# aq_mx_v1-3-0c.net
KiCad netlist of a schematic drawn in EAGLE
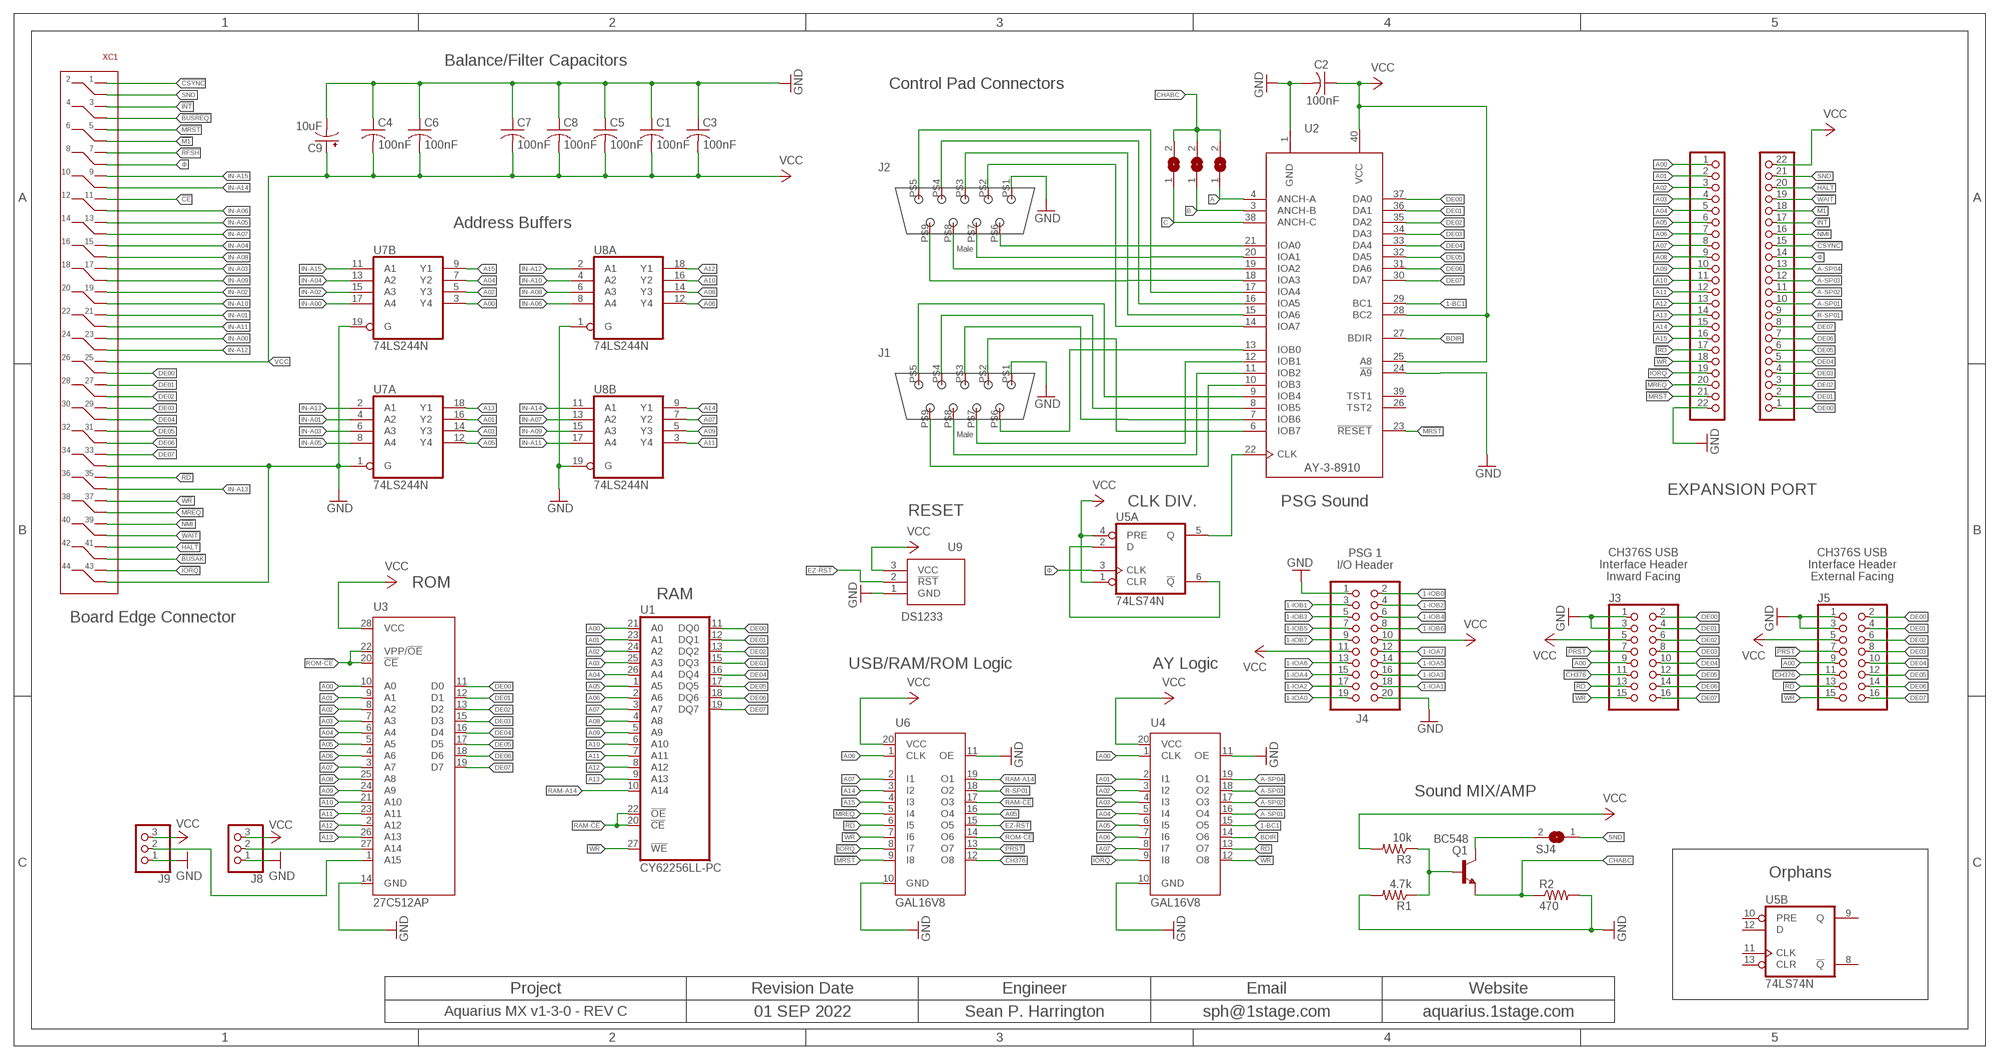
[diagram p0: schematic, sheet 1]

(export (version "E")
  (design (tool "Eeschema 10.0.6"))
  (components
    (comp (ref "C1")
      (value "100nF")
      (footprint "eagle-import:C050-025X075")
      (libsource (lib "eagle-import") (part "C-US050-025X075"))
    )
    (comp (ref "C2")
      (value "100nF")
      (footprint "eagle-import:C050-025X075")
      (libsource (lib "eagle-import") (part "C-US050-025X075"))
    )
    (comp (ref "C3")
      (value "100nF")
      (footprint "eagle-import:C050-025X075")
      (libsource (lib "eagle-import") (part "C-US050-025X075"))
    )
    (comp (ref "C4")
      (value "100nF")
      (footprint "eagle-import:C050-025X075")
      (libsource (lib "eagle-import") (part "C-US050-025X075"))
    )
    (comp (ref "C5")
      (value "100nF")
      (footprint "eagle-import:C050-025X075")
      (libsource (lib "eagle-import") (part "C-US050-025X075"))
    )
    (comp (ref "C6")
      (value "100nF")
      (footprint "eagle-import:C050-025X075")
      (libsource (lib "eagle-import") (part "C-US050-025X075"))
    )
    (comp (ref "C7")
      (value "100nF")
      (footprint "eagle-import:C050-025X075")
      (libsource (lib "eagle-import") (part "C-US050-025X075"))
    )
    (comp (ref "C8")
      (value "100nF")
      (footprint "eagle-import:C050-025X075")
      (libsource (lib "eagle-import") (part "C-US050-025X075"))
    )
    (comp (ref "C9")
      (value "10uF")
      (footprint "eagle-import:E22-6")
      (libsource (lib "eagle-import") (part "CPOL-USE22-6AXIAL"))
    )
    (comp (ref "J1")
      (value "DB9-MALE-RA")
      (footprint "eagle-import:DB9-MALE-RA")
      (libsource (lib "eagle-import") (part "DB9-MALE-RA"))
    )
    (comp (ref "J2")
      (value "DB9-MALE-RA")
      (footprint "eagle-import:DB9-MALE-RA")
      (libsource (lib "eagle-import") (part "DB9-MALE-RA"))
    )
    (comp (ref "J3")
      (value "PINHD-2X8")
      (footprint "eagle-import:2X08")
      (libsource (lib "eagle-import") (part "PINHD-2X8"))
    )
    (comp (ref "J4")
      (value "PINHD-2X10")
      (footprint "eagle-import:2X10")
      (libsource (lib "eagle-import") (part "PINHD-2X10"))
    )
    (comp (ref "J5")
      (value "PINHD-2X8")
      (footprint "eagle-import:2X08")
      (libsource (lib "eagle-import") (part "PINHD-2X8"))
    )
    (comp (ref "J6")
      (value "PINHD-1X22")
      (footprint "eagle-import:1X22")
      (libsource (lib "eagle-import") (part "PINHD-1X22"))
    )
    (comp (ref "J7")
      (value "PINHD-1X22")
      (footprint "eagle-import:1X22")
      (libsource (lib "eagle-import") (part "PINHD-1X22"))
    )
    (comp (ref "J8")
      (value "PINHD-1X3")
      (footprint "eagle-import:1X03")
      (libsource (lib "eagle-import") (part "PINHD-1X3"))
    )
    (comp (ref "J9")
      (value "PINHD-1X3")
      (footprint "eagle-import:1X03")
      (libsource (lib "eagle-import") (part "PINHD-1X3"))
    )
    (comp (ref "Q1")
      (value "BC548")
      (footprint "eagle-import:TO92-CBE")
      (libsource (lib "eagle-import") (part "-NPN-TO92-CBEBC548"))
    )
    (comp (ref "R1")
      (value "4.7k")
      (footprint "eagle-import:0204_7")
      (libsource (lib "eagle-import") (part "R-US_0204/7"))
    )
    (comp (ref "R2")
      (value "470")
      (footprint "eagle-import:0204_7")
      (libsource (lib "eagle-import") (part "R-US_0204/7"))
    )
    (comp (ref "R3")
      (value "10k")
      (footprint "eagle-import:0204_7")
      (libsource (lib "eagle-import") (part "R-US_0204/7"))
    )
    (comp (ref "SJ1") (value "SJ") (footprint "eagle-import:SJ") (libsource (lib "eagle-import") (part "SJ")))
    (comp (ref "SJ2") (value "SJ") (footprint "eagle-import:SJ") (libsource (lib "eagle-import") (part "SJ")))
    (comp (ref "SJ3") (value "SJ") (footprint "eagle-import:SJ") (libsource (lib "eagle-import") (part "SJ")))
    (comp (ref "SJ4") (value "SJ") (footprint "eagle-import:SJ") (libsource (lib "eagle-import") (part "SJ")))
    (comp (ref "U1")
      (value "CY62256LL-PC")
      (footprint "eagle-import:DIL28-6")
      (libsource (lib "eagle-import") (part "CY62256LL-?PC"))
    )
    (comp (ref "U2")
      (value "AY-3-8910")
      (footprint "eagle-import:RAD38910-DIL40-6")
      (libsource (lib "eagle-import") (part "RAD38910DIL40-6"))
    )
    (comp (ref "U3")
      (value "27C512AP")
      (footprint "eagle-import:DIL28-6")
      (fields (field (name "MPN") "M27C512-90B6"))
      (libsource (lib "eagle-import") (part "27512APC"))
    )
    (comp (ref "U4")
      (value "GAL16V8")
      (footprint "eagle-import:DIL20")
      (fields (field (name "MPN") "ATF16V8CZ-15PU"))
      (libsource (lib "eagle-import") (part "ATF16V8BP3"))
    )
    (comp (ref "U5")
      (value "74LS74N")
      (footprint "eagle-import:DIL14")
      (libsource (lib "eagle-import") (part "7474NLS"))
    )
    (comp (ref "U6")
      (value "GAL16V8")
      (footprint "eagle-import:DIL20")
      (fields (field (name "MPN") "ATF16V8CZ-15PU"))
      (libsource (lib "eagle-import") (part "ATF16V8BP3"))
    )
    (comp (ref "U7")
      (value "74LS244N")
      (footprint "eagle-import:DIL20")
      (libsource (lib "eagle-import") (part "74244NLS"))
    )
    (comp (ref "U8")
      (value "74LS244N")
      (footprint "eagle-import:DIL20")
      (libsource (lib "eagle-import") (part "74244NLS"))
    )
    (comp (ref "U9")
      (value "DS1233")
      (footprint "eagle-import:TO-92")
      (fields
        (field (name "ARROW_PART_NUMBER") "DS1233-10+")
        (field (name "MOUSER_PART_NUMBER") "700-DS1233-10")
      )
      (libsource (lib "eagle-import") (part "DS1233-10+"))
    )
    (comp (ref "XC1")
      (value "AQ-CART-EDGE")
      (footprint "eagle-import:AQ-CART-EDGE")
      (libsource (lib "eagle-import") (part "AQ-CART-EDGE"))
    )
  )
  (nets
    (net (code "1") (name "/EZ-~{RST}") (class "Default")
      (node (ref "U6") (pin "15") (pinfunction "O5_15") (pintype "output"))
      (node (ref "U9") (pin "2") (pinfunction "~{RST}_2") (pintype "input"))
    )
    (net (code "2") (name "/RAM-~{CE}") (class "Default")
      (node (ref "U1") (pin "20") (pinfunction "~{CE}_20") (pintype "input"))
      (node (ref "U1") (pin "22") (pinfunction "~{OE}_22") (pintype "input"))
      (node (ref "U6") (pin "17") (pinfunction "O3_17") (pintype "output"))
    )
    (net (code "3") (name "/ROM-~{CE}") (class "Default")
      (node (ref "U3") (pin "20") (pinfunction "~{CE}_20") (pintype "input"))
      (node (ref "U3") (pin "22") (pinfunction "VPP/~{OE}_22") (pintype "input"))
      (node (ref "U6") (pin "14") (pinfunction "O6_14") (pintype "output"))
    )
    (net (code "4") (name "/~{BUSAK}") (class "Default")
      (node (ref "XC1") (pin "P$42") (pinfunction "X42_P$42") (pintype "bidirectional"))
    )
    (net (code "5") (name "/~{BUSREQ}") (class "Default")
      (node (ref "XC1") (pin "P$4") (pinfunction "X4_P$4") (pintype "bidirectional"))
    )
    (net (code "6") (name "/~{CE}") (class "Default")
      (node (ref "XC1") (pin "P$11") (pinfunction "X11_P$11") (pintype "bidirectional"))
    )
    (net (code "7") (name "/~{CH376}") (class "Default")
      (node (ref "J3") (pin "11") (pinfunction "11_11") (pintype "passive"))
      (node (ref "J5") (pin "11") (pinfunction "11_11") (pintype "passive"))
      (node (ref "U6") (pin "12") (pinfunction "O8_12") (pintype "output"))
    )
    (net (code "8") (name "/~{CSYNC}") (class "Default")
      (node (ref "J6") (pin "15") (pinfunction "15_15") (pintype "passive"))
      (node (ref "XC1") (pin "P$1") (pinfunction "X1_P$1") (pintype "bidirectional"))
    )
    (net (code "9") (name "/~{HALT}") (class "Default")
      (node (ref "J6") (pin "20") (pinfunction "20_20") (pintype "passive"))
      (node (ref "XC1") (pin "P$41") (pinfunction "X41_P$41") (pintype "bidirectional"))
    )
    (net (code "10") (name "/~{INT}") (class "Default")
      (node (ref "J6") (pin "17") (pinfunction "17_17") (pintype "passive"))
      (node (ref "XC1") (pin "P$3") (pinfunction "X3_P$3") (pintype "bidirectional"))
    )
    (net (code "11") (name "/~{IORQ}") (class "Default")
      (node (ref "J7") (pin "19") (pinfunction "19_19") (pintype "passive"))
      (node (ref "U4") (pin "9") (pinfunction "I8_9") (pintype "input"))
      (node (ref "U6") (pin "8") (pinfunction "I7_8") (pintype "input"))
      (node (ref "XC1") (pin "P$43") (pinfunction "X43_P$43") (pintype "bidirectional"))
    )
    (net (code "12") (name "/~{M1}") (class "Default")
      (node (ref "J6") (pin "18") (pinfunction "18_18") (pintype "passive"))
      (node (ref "XC1") (pin "P$6") (pinfunction "X6_P$6") (pintype "bidirectional"))
    )
    (net (code "13") (name "/~{MREQ}") (class "Default")
      (node (ref "J7") (pin "20") (pinfunction "20_20") (pintype "passive"))
      (node (ref "U6") (pin "5") (pinfunction "I4_5") (pintype "input"))
      (node (ref "XC1") (pin "P$38") (pinfunction "X38_P$38") (pintype "bidirectional"))
    )
    (net (code "14") (name "/~{MRST}") (class "Default")
      (node (ref "J7") (pin "21") (pinfunction "21_21") (pintype "passive"))
      (node (ref "U2") (pin "23") (pinfunction "~{RESET}_23") (pintype "bidirectional"))
      (node (ref "U6") (pin "9") (pinfunction "I8_9") (pintype "input"))
      (node (ref "XC1") (pin "P$5") (pinfunction "X5_P$5") (pintype "bidirectional"))
    )
    (net (code "15") (name "/~{NMI}") (class "Default")
      (node (ref "J6") (pin "16") (pinfunction "16_16") (pintype "passive"))
      (node (ref "XC1") (pin "P$39") (pinfunction "X39_P$39") (pintype "bidirectional"))
    )
    (net (code "16") (name "/~{PRST}") (class "Default")
      (node (ref "J3") (pin "7") (pinfunction "7_7") (pintype "passive"))
      (node (ref "J5") (pin "7") (pinfunction "7_7") (pintype "passive"))
      (node (ref "U6") (pin "13") (pinfunction "O7_13") (pintype "output"))
    )
    (net (code "17") (name "/~{RD}") (class "Default")
      (node (ref "J3") (pin "13") (pinfunction "13_13") (pintype "passive"))
      (node (ref "J5") (pin "13") (pinfunction "13_13") (pintype "passive"))
      (node (ref "J7") (pin "17") (pinfunction "17_17") (pintype "passive"))
      (node (ref "U4") (pin "13") (pinfunction "O7_13") (pintype "output"))
      (node (ref "U6") (pin "6") (pinfunction "I5_6") (pintype "input"))
      (node (ref "XC1") (pin "P$35") (pinfunction "X35_P$35") (pintype "bidirectional"))
    )
    (net (code "18") (name "/~{RFSH}") (class "Default")
      (node (ref "XC1") (pin "P$7") (pinfunction "X7_P$7") (pintype "bidirectional"))
    )
    (net (code "19") (name "/~{WAIT}") (class "Default")
      (node (ref "J6") (pin "19") (pinfunction "19_19") (pintype "passive"))
      (node (ref "XC1") (pin "P$40") (pinfunction "X40_P$40") (pintype "bidirectional"))
    )
    (net (code "20") (name "/~{WR}") (class "Default")
      (node (ref "J3") (pin "15") (pinfunction "15_15") (pintype "passive"))
      (node (ref "J5") (pin "15") (pinfunction "15_15") (pintype "passive"))
      (node (ref "J7") (pin "18") (pinfunction "18_18") (pintype "passive"))
      (node (ref "U1") (pin "27") (pinfunction "~{WE}_27") (pintype "input"))
      (node (ref "U4") (pin "12") (pinfunction "O8_12") (pintype "output"))
      (node (ref "U6") (pin "7") (pinfunction "I6_7") (pintype "input"))
      (node (ref "XC1") (pin "P$37") (pinfunction "X37_P$37") (pintype "bidirectional"))
    )
    (net (code "21") (name "1-BC1") (class "Default")
      (node (ref "U2") (pin "29") (pinfunction "BC1_29") (pintype "bidirectional"))
      (node (ref "U4") (pin "15") (pinfunction "O5_15") (pintype "output"))
    )
    (net (code "22") (name "1-IOA0") (class "Default")
      (node (ref "J2") (pin "P$6") (pinfunction "P$6_P$6") (pintype "bidirectional"))
      (node (ref "J4") (pin "19") (pinfunction "19_19") (pintype "passive"))
      (node (ref "U2") (pin "21") (pinfunction "IOA0_21") (pintype "bidirectional"))
    )
    (net (code "23") (name "1-IOA1") (class "Default")
      (node (ref "J2") (pin "P$7") (pinfunction "P$7_P$7") (pintype "bidirectional"))
      (node (ref "J4") (pin "18") (pinfunction "18_18") (pintype "passive"))
      (node (ref "U2") (pin "20") (pinfunction "IOA1_20") (pintype "bidirectional"))
    )
    (net (code "24") (name "1-IOA2") (class "Default")
      (node (ref "J2") (pin "P$8") (pinfunction "P$8_P$8") (pintype "bidirectional"))
      (node (ref "J4") (pin "17") (pinfunction "17_17") (pintype "passive"))
      (node (ref "U2") (pin "19") (pinfunction "IOA2_19") (pintype "bidirectional"))
    )
    (net (code "25") (name "1-IOA3") (class "Default")
      (node (ref "J2") (pin "P$9") (pinfunction "P$9_P$9") (pintype "bidirectional"))
      (node (ref "J4") (pin "16") (pinfunction "16_16") (pintype "passive"))
      (node (ref "U2") (pin "18") (pinfunction "IOA3_18") (pintype "bidirectional"))
    )
    (net (code "26") (name "1-IOA4") (class "Default")
      (node (ref "J2") (pin "P$5") (pinfunction "P$5_P$5") (pintype "bidirectional"))
      (node (ref "J4") (pin "15") (pinfunction "15_15") (pintype "passive"))
      (node (ref "U2") (pin "17") (pinfunction "IOA4_17") (pintype "bidirectional"))
    )
    (net (code "27") (name "1-IOA5") (class "Default")
      (node (ref "J2") (pin "P$4") (pinfunction "P$4_P$4") (pintype "bidirectional"))
      (node (ref "J4") (pin "14") (pinfunction "14_14") (pintype "passive"))
      (node (ref "U2") (pin "16") (pinfunction "IOA5_16") (pintype "bidirectional"))
    )
    (net (code "28") (name "1-IOA6") (class "Default")
      (node (ref "J2") (pin "P$3") (pinfunction "P$3_P$3") (pintype "bidirectional"))
      (node (ref "J4") (pin "13") (pinfunction "13_13") (pintype "passive"))
      (node (ref "U2") (pin "15") (pinfunction "IOA6_15") (pintype "bidirectional"))
    )
    (net (code "29") (name "1-IOA7") (class "Default")
      (node (ref "J2") (pin "P$2") (pinfunction "P$2_P$2") (pintype "bidirectional"))
      (node (ref "J4") (pin "12") (pinfunction "12_12") (pintype "passive"))
      (node (ref "U2") (pin "14") (pinfunction "IOA7_14") (pintype "bidirectional"))
    )
    (net (code "30") (name "1-IOB0") (class "Default")
      (node (ref "J1") (pin "P$6") (pinfunction "P$6_P$6") (pintype "bidirectional"))
      (node (ref "J4") (pin "2") (pinfunction "2_2") (pintype "passive"))
      (node (ref "U2") (pin "13") (pinfunction "IOB0_13") (pintype "bidirectional"))
    )
    (net (code "31") (name "1-IOB1") (class "Default")
      (node (ref "J1") (pin "P$7") (pinfunction "P$7_P$7") (pintype "bidirectional"))
      (node (ref "J4") (pin "3") (pinfunction "3_3") (pintype "passive"))
      (node (ref "U2") (pin "12") (pinfunction "IOB1_12") (pintype "bidirectional"))
    )
    (net (code "32") (name "1-IOB2") (class "Default")
      (node (ref "J1") (pin "P$8") (pinfunction "P$8_P$8") (pintype "bidirectional"))
      (node (ref "J4") (pin "4") (pinfunction "4_4") (pintype "passive"))
      (node (ref "U2") (pin "11") (pinfunction "IOB2_11") (pintype "bidirectional"))
    )
    (net (code "33") (name "1-IOB3") (class "Default")
      (node (ref "J1") (pin "P$9") (pinfunction "P$9_P$9") (pintype "bidirectional"))
      (node (ref "J4") (pin "5") (pinfunction "5_5") (pintype "passive"))
      (node (ref "U2") (pin "10") (pinfunction "IOB3_10") (pintype "bidirectional"))
    )
    (net (code "34") (name "1-IOB4") (class "Default")
      (node (ref "J1") (pin "P$5") (pinfunction "P$5_P$5") (pintype "bidirectional"))
      (node (ref "J4") (pin "6") (pinfunction "6_6") (pintype "passive"))
      (node (ref "U2") (pin "9") (pinfunction "IOB4_9") (pintype "bidirectional"))
    )
    (net (code "35") (name "1-IOB5") (class "Default")
      (node (ref "J1") (pin "P$4") (pinfunction "P$4_P$4") (pintype "bidirectional"))
      (node (ref "J4") (pin "7") (pinfunction "7_7") (pintype "passive"))
      (node (ref "U2") (pin "8") (pinfunction "IOB5_8") (pintype "bidirectional"))
    )
    (net (code "36") (name "1-IOB6") (class "Default")
      (node (ref "J1") (pin "P$3") (pinfunction "P$3_P$3") (pintype "bidirectional"))
      (node (ref "J4") (pin "8") (pinfunction "8_8") (pintype "passive"))
      (node (ref "U2") (pin "7") (pinfunction "IOB6_7") (pintype "bidirectional"))
    )
    (net (code "37") (name "1-IOB7") (class "Default")
      (node (ref "J1") (pin "P$2") (pinfunction "P$2_P$2") (pintype "bidirectional"))
      (node (ref "J4") (pin "9") (pinfunction "9_9") (pintype "passive"))
      (node (ref "U2") (pin "6") (pinfunction "IOB7_6") (pintype "bidirectional"))
    )
    (net (code "38") (name "A") (class "Default")
      (node (ref "SJ1") (pin "1") (pinfunction "1_1") (pintype "passive"))
      (node (ref "U2") (pin "4") (pinfunction "ANCH-A_4") (pintype "bidirectional"))
    )
    (net (code "39") (name "A-SP01") (class "Default")
      (node (ref "J6") (pin "10") (pinfunction "10_10") (pintype "passive"))
      (node (ref "U4") (pin "16") (pinfunction "O4_16") (pintype "output"))
    )
    (net (code "40") (name "A-SP02") (class "Default")
      (node (ref "J6") (pin "11") (pinfunction "11_11") (pintype "passive"))
      (node (ref "U4") (pin "17") (pinfunction "O3_17") (pintype "output"))
    )
    (net (code "41") (name "A-SP03") (class "Default")
      (node (ref "J6") (pin "12") (pinfunction "12_12") (pintype "passive"))
      (node (ref "U4") (pin "18") (pinfunction "O2_18") (pintype "output"))
    )
    (net (code "42") (name "A-SP04") (class "Default")
      (node (ref "J6") (pin "13") (pinfunction "13_13") (pintype "passive"))
      (node (ref "U4") (pin "19") (pinfunction "O1_19") (pintype "output"))
    )
    (net (code "43") (name "A00") (class "Default")
      (node (ref "J3") (pin "9") (pinfunction "9_9") (pintype "passive"))
      (node (ref "J5") (pin "9") (pinfunction "9_9") (pintype "passive"))
      (node (ref "J7") (pin "1") (pinfunction "1_1") (pintype "passive"))
      (node (ref "U1") (pin "21") (pinfunction "A0_21") (pintype "input"))
      (node (ref "U3") (pin "10") (pinfunction "A0_10") (pintype "input"))
      (node (ref "U4") (pin "1") (pinfunction "CLK_1") (pintype "input"))
      (node (ref "U7") (pin "3") (pinfunction "Y4_3") (pintype "tri_state"))
    )
    (net (code "44") (name "A01") (class "Default")
      (node (ref "J7") (pin "2") (pinfunction "2_2") (pintype "passive"))
      (node (ref "U1") (pin "23") (pinfunction "A1_23") (pintype "input"))
      (node (ref "U3") (pin "9") (pinfunction "A1_9") (pintype "input"))
      (node (ref "U4") (pin "2") (pinfunction "I1_2") (pintype "input"))
      (node (ref "U7") (pin "16") (pinfunction "Y2_16") (pintype "tri_state"))
    )
    (net (code "45") (name "A02") (class "Default")
      (node (ref "J7") (pin "3") (pinfunction "3_3") (pintype "passive"))
      (node (ref "U1") (pin "24") (pinfunction "A2_24") (pintype "input"))
      (node (ref "U3") (pin "8") (pinfunction "A2_8") (pintype "input"))
      (node (ref "U4") (pin "3") (pinfunction "I2_3") (pintype "input"))
      (node (ref "U7") (pin "5") (pinfunction "Y3_5") (pintype "tri_state"))
    )
    (net (code "46") (name "A03") (class "Default")
      (node (ref "J7") (pin "4") (pinfunction "4_4") (pintype "passive"))
      (node (ref "U1") (pin "25") (pinfunction "A3_25") (pintype "input"))
      (node (ref "U3") (pin "7") (pinfunction "A3_7") (pintype "input"))
      (node (ref "U4") (pin "4") (pinfunction "I3_4") (pintype "input"))
      (node (ref "U7") (pin "14") (pinfunction "Y3_14") (pintype "tri_state"))
    )
    (net (code "47") (name "A04") (class "Default")
      (node (ref "J7") (pin "5") (pinfunction "5_5") (pintype "passive"))
      (node (ref "U1") (pin "26") (pinfunction "A4_26") (pintype "input"))
      (node (ref "U3") (pin "6") (pinfunction "A4_6") (pintype "input"))
      (node (ref "U4") (pin "5") (pinfunction "I4_5") (pintype "input"))
      (node (ref "U7") (pin "7") (pinfunction "Y2_7") (pintype "tri_state"))
    )
    (net (code "48") (name "A05") (class "Default")
      (node (ref "J7") (pin "6") (pinfunction "6_6") (pintype "passive"))
      (node (ref "U1") (pin "1") (pinfunction "A5_1") (pintype "input"))
      (node (ref "U3") (pin "5") (pinfunction "A5_5") (pintype "input"))
      (node (ref "U4") (pin "6") (pinfunction "I5_6") (pintype "input"))
      (node (ref "U6") (pin "16") (pinfunction "O4_16") (pintype "output"))
      (node (ref "U7") (pin "12") (pinfunction "Y4_12") (pintype "tri_state"))
    )
    (net (code "49") (name "A06") (class "Default")
      (node (ref "J7") (pin "7") (pinfunction "7_7") (pintype "passive"))
      (node (ref "U1") (pin "2") (pinfunction "A6_2") (pintype "input"))
      (node (ref "U3") (pin "4") (pinfunction "A6_4") (pintype "input"))
      (node (ref "U4") (pin "7") (pinfunction "I6_7") (pintype "input"))
      (node (ref "U6") (pin "1") (pinfunction "CLK_1") (pintype "input"))
      (node (ref "U8") (pin "12") (pinfunction "Y4_12") (pintype "tri_state"))
    )
    (net (code "50") (name "A07") (class "Default")
      (node (ref "J7") (pin "8") (pinfunction "8_8") (pintype "passive"))
      (node (ref "U1") (pin "3") (pinfunction "A7_3") (pintype "input"))
      (node (ref "U3") (pin "3") (pinfunction "A7_3") (pintype "input"))
      (node (ref "U4") (pin "8") (pinfunction "I7_8") (pintype "input"))
      (node (ref "U6") (pin "2") (pinfunction "I1_2") (pintype "input"))
      (node (ref "U8") (pin "7") (pinfunction "Y2_7") (pintype "tri_state"))
    )
    (net (code "51") (name "A08") (class "Default")
      (node (ref "J7") (pin "9") (pinfunction "9_9") (pintype "passive"))
      (node (ref "U1") (pin "4") (pinfunction "A8_4") (pintype "input"))
      (node (ref "U3") (pin "25") (pinfunction "A8_25") (pintype "input"))
      (node (ref "U8") (pin "14") (pinfunction "Y3_14") (pintype "tri_state"))
    )
    (net (code "52") (name "A09") (class "Default")
      (node (ref "J7") (pin "10") (pinfunction "10_10") (pintype "passive"))
      (node (ref "U1") (pin "5") (pinfunction "A9_5") (pintype "input"))
      (node (ref "U3") (pin "24") (pinfunction "A9_24") (pintype "input"))
      (node (ref "U8") (pin "5") (pinfunction "Y3_5") (pintype "tri_state"))
    )
    (net (code "53") (name "A10") (class "Default")
      (node (ref "J7") (pin "11") (pinfunction "11_11") (pintype "passive"))
      (node (ref "U1") (pin "6") (pinfunction "A10_6") (pintype "input"))
      (node (ref "U3") (pin "21") (pinfunction "A10_21") (pintype "input"))
      (node (ref "U8") (pin "16") (pinfunction "Y2_16") (pintype "tri_state"))
    )
    (net (code "54") (name "A11") (class "Default")
      (node (ref "J7") (pin "12") (pinfunction "12_12") (pintype "passive"))
      (node (ref "U1") (pin "7") (pinfunction "A11_7") (pintype "input"))
      (node (ref "U3") (pin "23") (pinfunction "A11_23") (pintype "input"))
      (node (ref "U8") (pin "3") (pinfunction "Y4_3") (pintype "tri_state"))
    )
    (net (code "55") (name "A12") (class "Default")
      (node (ref "J7") (pin "13") (pinfunction "13_13") (pintype "passive"))
      (node (ref "U1") (pin "8") (pinfunction "A12_8") (pintype "input"))
      (node (ref "U3") (pin "2") (pinfunction "A12_2") (pintype "input"))
      (node (ref "U8") (pin "18") (pinfunction "Y1_18") (pintype "tri_state"))
    )
    (net (code "56") (name "A13") (class "Default")
      (node (ref "J7") (pin "14") (pinfunction "14_14") (pintype "passive"))
      (node (ref "U1") (pin "9") (pinfunction "A13_9") (pintype "input"))
      (node (ref "U3") (pin "26") (pinfunction "A13_26") (pintype "input"))
      (node (ref "U7") (pin "18") (pinfunction "Y1_18") (pintype "tri_state"))
    )
    (net (code "57") (name "A14") (class "Default")
      (node (ref "J7") (pin "15") (pinfunction "15_15") (pintype "passive"))
      (node (ref "U6") (pin "3") (pinfunction "I2_3") (pintype "input"))
      (node (ref "U8") (pin "9") (pinfunction "Y1_9") (pintype "tri_state"))
    )
    (net (code "58") (name "A15") (class "Default")
      (node (ref "J7") (pin "16") (pinfunction "16_16") (pintype "passive"))
      (node (ref "U6") (pin "4") (pinfunction "I3_4") (pintype "input"))
      (node (ref "U7") (pin "9") (pinfunction "Y1_9") (pintype "tri_state"))
    )
    (net (code "59") (name "B") (class "Default")
      (node (ref "SJ2") (pin "1") (pinfunction "1_1") (pintype "passive"))
      (node (ref "U2") (pin "3") (pinfunction "ANCH-B_3") (pintype "bidirectional"))
    )
    (net (code "60") (name "BDIR") (class "Default")
      (node (ref "U2") (pin "27") (pinfunction "BDIR_27") (pintype "bidirectional"))
      (node (ref "U4") (pin "14") (pinfunction "O6_14") (pintype "output"))
    )
    (net (code "61") (name "C") (class "Default")
      (node (ref "SJ3") (pin "1") (pinfunction "1_1") (pintype "passive"))
      (node (ref "U2") (pin "38") (pinfunction "ANCH-C_38") (pintype "bidirectional"))
    )
    (net (code "62") (name "CHABC") (class "Default")
      (node (ref "Q1") (pin "E") (pinfunction "E_E") (pintype "passive"))
      (node (ref "R2") (pin "1") (pinfunction "1_1") (pintype "passive"))
      (node (ref "SJ1") (pin "2") (pinfunction "2_2") (pintype "passive"))
      (node (ref "SJ2") (pin "2") (pinfunction "2_2") (pintype "passive"))
      (node (ref "SJ3") (pin "2") (pinfunction "2_2") (pintype "passive"))
    )
    (net (code "63") (name "DE00") (class "Default")
      (node (ref "J3") (pin "2") (pinfunction "2_2") (pintype "passive"))
      (node (ref "J5") (pin "2") (pinfunction "2_2") (pintype "passive"))
      (node (ref "J6") (pin "1") (pinfunction "1_1") (pintype "passive"))
      (node (ref "U1") (pin "11") (pinfunction "DQ0_11") (pintype "bidirectional"))
      (node (ref "U2") (pin "37") (pinfunction "DA0_37") (pintype "bidirectional"))
      (node (ref "U3") (pin "11") (pinfunction "D0_11") (pintype "tri_state"))
      (node (ref "XC1") (pin "P$26") (pinfunction "X26_P$26") (pintype "bidirectional"))
    )
    (net (code "64") (name "DE01") (class "Default")
      (node (ref "J3") (pin "4") (pinfunction "4_4") (pintype "passive"))
      (node (ref "J5") (pin "4") (pinfunction "4_4") (pintype "passive"))
      (node (ref "J6") (pin "2") (pinfunction "2_2") (pintype "passive"))
      (node (ref "U1") (pin "12") (pinfunction "DQ1_12") (pintype "bidirectional"))
      (node (ref "U2") (pin "36") (pinfunction "DA1_36") (pintype "bidirectional"))
      (node (ref "U3") (pin "12") (pinfunction "D1_12") (pintype "tri_state"))
      (node (ref "XC1") (pin "P$27") (pinfunction "X27_P$27") (pintype "bidirectional"))
    )
    (net (code "65") (name "DE02") (class "Default")
      (node (ref "J3") (pin "6") (pinfunction "6_6") (pintype "passive"))
      (node (ref "J5") (pin "6") (pinfunction "6_6") (pintype "passive"))
      (node (ref "J6") (pin "3") (pinfunction "3_3") (pintype "passive"))
      (node (ref "U1") (pin "13") (pinfunction "DQ2_13") (pintype "bidirectional"))
      (node (ref "U2") (pin "35") (pinfunction "DA2_35") (pintype "bidirectional"))
      (node (ref "U3") (pin "13") (pinfunction "D2_13") (pintype "tri_state"))
      (node (ref "XC1") (pin "P$28") (pinfunction "X28_P$28") (pintype "bidirectional"))
    )
    (net (code "66") (name "DE03") (class "Default")
      (node (ref "J3") (pin "8") (pinfunction "8_8") (pintype "passive"))
      (node (ref "J5") (pin "8") (pinfunction "8_8") (pintype "passive"))
      (node (ref "J6") (pin "4") (pinfunction "4_4") (pintype "passive"))
      (node (ref "U1") (pin "15") (pinfunction "DQ3_15") (pintype "bidirectional"))
      (node (ref "U2") (pin "34") (pinfunction "DA3_34") (pintype "bidirectional"))
      (node (ref "U3") (pin "15") (pinfunction "D3_15") (pintype "tri_state"))
      (node (ref "XC1") (pin "P$29") (pinfunction "X29_P$29") (pintype "bidirectional"))
    )
    (net (code "67") (name "DE04") (class "Default")
      (node (ref "J3") (pin "10") (pinfunction "10_10") (pintype "passive"))
      (node (ref "J5") (pin "10") (pinfunction "10_10") (pintype "passive"))
      (node (ref "J6") (pin "5") (pinfunction "5_5") (pintype "passive"))
      (node (ref "U1") (pin "16") (pinfunction "DQ4_16") (pintype "bidirectional"))
      (node (ref "U2") (pin "33") (pinfunction "DA4_33") (pintype "bidirectional"))
      (node (ref "U3") (pin "16") (pinfunction "D4_16") (pintype "tri_state"))
      (node (ref "XC1") (pin "P$30") (pinfunction "X30_P$30") (pintype "bidirectional"))
    )
    (net (code "68") (name "DE05") (class "Default")
      (node (ref "J3") (pin "12") (pinfunction "12_12") (pintype "passive"))
      (node (ref "J5") (pin "12") (pinfunction "12_12") (pintype "passive"))
      (node (ref "J6") (pin "6") (pinfunction "6_6") (pintype "passive"))
      (node (ref "U1") (pin "17") (pinfunction "DQ5_17") (pintype "bidirectional"))
      (node (ref "U2") (pin "32") (pinfunction "DA5_32") (pintype "bidirectional"))
      (node (ref "U3") (pin "17") (pinfunction "D5_17") (pintype "tri_state"))
      (node (ref "XC1") (pin "P$31") (pinfunction "X31_P$31") (pintype "bidirectional"))
    )
    (net (code "69") (name "DE06") (class "Default")
      (node (ref "J3") (pin "14") (pinfunction "14_14") (pintype "passive"))
      (node (ref "J5") (pin "14") (pinfunction "14_14") (pintype "passive"))
      (node (ref "J6") (pin "7") (pinfunction "7_7") (pintype "passive"))
      (node (ref "U1") (pin "18") (pinfunction "DQ6_18") (pintype "bidirectional"))
      (node (ref "U2") (pin "31") (pinfunction "DA6_31") (pintype "bidirectional"))
      (node (ref "U3") (pin "18") (pinfunction "D6_18") (pintype "tri_state"))
      (node (ref "XC1") (pin "P$32") (pinfunction "X32_P$32") (pintype "bidirectional"))
    )
    (net (code "70") (name "DE07") (class "Default")
      (node (ref "J3") (pin "16") (pinfunction "16_16") (pintype "passive"))
      (node (ref "J5") (pin "16") (pinfunction "16_16") (pintype "passive"))
      (node (ref "J6") (pin "8") (pinfunction "8_8") (pintype "passive"))
      (node (ref "U1") (pin "19") (pinfunction "DQ7_19") (pintype "bidirectional"))
      (node (ref "U2") (pin "30") (pinfunction "DA7_30") (pintype "bidirectional"))
      (node (ref "U3") (pin "19") (pinfunction "D7_19") (pintype "tri_state"))
      (node (ref "XC1") (pin "P$33") (pinfunction "X33_P$33") (pintype "bidirectional"))
    )
    (net (code "71") (name "GND") (class "Default")
      (node (ref "C1") (pin "1") (pinfunction "1_1") (pintype "passive"))
      (node (ref "C2") (pin "2") (pinfunction "2_2") (pintype "passive"))
      (node (ref "C3") (pin "1") (pinfunction "1_1") (pintype "passive"))
      (node (ref "C4") (pin "1") (pinfunction "1_1") (pintype "passive"))
      (node (ref "C5") (pin "1") (pinfunction "1_1") (pintype "passive"))
      (node (ref "C6") (pin "1") (pinfunction "1_1") (pintype "passive"))
      (node (ref "C7") (pin "1") (pinfunction "1_1") (pintype "passive"))
      (node (ref "C8") (pin "1") (pinfunction "1_1") (pintype "passive"))
      (node (ref "C9") (pin "-") (pinfunction "-_-") (pintype "passive"))
      (node (ref "J1") (pin "P$1") (pinfunction "P$1_P$1") (pintype "bidirectional"))
      (node (ref "J2") (pin "P$1") (pinfunction "P$1_P$1") (pintype "bidirectional"))
      (node (ref "J3") (pin "1") (pinfunction "1_1") (pintype "passive"))
      (node (ref "J3") (pin "3") (pinfunction "3_3") (pintype "passive"))
      (node (ref "J4") (pin "1") (pinfunction "1_1") (pintype "passive"))
      (node (ref "J4") (pin "20") (pinfunction "20_20") (pintype "passive"))
      (node (ref "J5") (pin "1") (pinfunction "1_1") (pintype "passive"))
      (node (ref "J5") (pin "3") (pinfunction "3_3") (pintype "passive"))
      (node (ref "J7") (pin "22") (pinfunction "22_22") (pintype "passive"))
      (node (ref "J8") (pin "1") (pinfunction "1_1") (pintype "passive"))
      (node (ref "J9") (pin "1") (pinfunction "1_1") (pintype "passive"))
      (node (ref "R1") (pin "2") (pinfunction "2_2") (pintype "passive"))
      (node (ref "R2") (pin "2") (pinfunction "2_2") (pintype "passive"))
      (node (ref "U2") (pin "1") (pinfunction "GND_1") (pintype "power_in"))
      (node (ref "U2") (pin "24") (pinfunction "~{A9}_24") (pintype "bidirectional"))
      (node (ref "U3") (pin "14") (pinfunction "GND_14") (pintype "power_in"))
      (node (ref "U4") (pin "10") (pinfunction "GND_10") (pintype "power_in"))
      (node (ref "U4") (pin "11") (pinfunction "OE_11") (pintype "input"))
      (node (ref "U6") (pin "10") (pinfunction "GND_10") (pintype "power_in"))
      (node (ref "U6") (pin "11") (pinfunction "OE_11") (pintype "input"))
      (node (ref "U7") (pin "1") (pinfunction "G_1") (pintype "input"))
      (node (ref "U7") (pin "19") (pinfunction "G_19") (pintype "input"))
      (node (ref "U8") (pin "1") (pinfunction "G_1") (pintype "input"))
      (node (ref "U8") (pin "19") (pinfunction "G_19") (pintype "input"))
      (node (ref "U9") (pin "1") (pinfunction "GND_1") (pintype "power_in"))
      (node (ref "XC1") (pin "P$34") (pinfunction "X34_P$34") (pintype "bidirectional"))
      (node (ref "XC1") (pin "P$44") (pinfunction "X44_P$44") (pintype "bidirectional"))
    )
    (net (code "72") (name "IN-A00") (class "Default")
      (node (ref "U7") (pin "17") (pinfunction "A4_17") (pintype "input"))
      (node (ref "XC1") (pin "P$23") (pinfunction "X23_P$23") (pintype "bidirectional"))
    )
    (net (code "73") (name "IN-A01") (class "Default")
      (node (ref "U7") (pin "4") (pinfunction "A2_4") (pintype "input"))
      (node (ref "XC1") (pin "P$21") (pinfunction "X21_P$21") (pintype "bidirectional"))
    )
    (net (code "74") (name "IN-A02") (class "Default")
      (node (ref "U7") (pin "15") (pinfunction "A3_15") (pintype "input"))
      (node (ref "XC1") (pin "P$19") (pinfunction "X19_P$19") (pintype "bidirectional"))
    )
    (net (code "75") (name "IN-A03") (class "Default")
      (node (ref "U7") (pin "6") (pinfunction "A3_6") (pintype "input"))
      (node (ref "XC1") (pin "P$17") (pinfunction "X17_P$17") (pintype "bidirectional"))
    )
    (net (code "76") (name "IN-A04") (class "Default")
      (node (ref "U7") (pin "13") (pinfunction "A2_13") (pintype "input"))
      (node (ref "XC1") (pin "P$15") (pinfunction "X15_P$15") (pintype "bidirectional"))
    )
    (net (code "77") (name "IN-A05") (class "Default")
      (node (ref "U7") (pin "8") (pinfunction "A4_8") (pintype "input"))
      (node (ref "XC1") (pin "P$13") (pinfunction "X13_P$13") (pintype "bidirectional"))
    )
    (net (code "78") (name "IN-A06") (class "Default")
      (node (ref "U8") (pin "8") (pinfunction "A4_8") (pintype "input"))
      (node (ref "XC1") (pin "P$12") (pinfunction "X12_P$12") (pintype "bidirectional"))
    )
    (net (code "79") (name "IN-A07") (class "Default")
      (node (ref "U8") (pin "13") (pinfunction "A2_13") (pintype "input"))
      (node (ref "XC1") (pin "P$14") (pinfunction "X14_P$14") (pintype "bidirectional"))
    )
    (net (code "80") (name "IN-A08") (class "Default")
      (node (ref "U8") (pin "6") (pinfunction "A3_6") (pintype "input"))
      (node (ref "XC1") (pin "P$16") (pinfunction "X16_P$16") (pintype "bidirectional"))
    )
    (net (code "81") (name "IN-A09") (class "Default")
      (node (ref "U8") (pin "15") (pinfunction "A3_15") (pintype "input"))
      (node (ref "XC1") (pin "P$18") (pinfunction "X18_P$18") (pintype "bidirectional"))
    )
    (net (code "82") (name "IN-A10") (class "Default")
      (node (ref "U8") (pin "4") (pinfunction "A2_4") (pintype "input"))
      (node (ref "XC1") (pin "P$20") (pinfunction "X20_P$20") (pintype "bidirectional"))
    )
    (net (code "83") (name "IN-A11") (class "Default")
      (node (ref "U8") (pin "17") (pinfunction "A4_17") (pintype "input"))
      (node (ref "XC1") (pin "P$22") (pinfunction "X22_P$22") (pintype "bidirectional"))
    )
    (net (code "84") (name "IN-A12") (class "Default")
      (node (ref "U8") (pin "2") (pinfunction "A1_2") (pintype "input"))
      (node (ref "XC1") (pin "P$24") (pinfunction "X24_P$24") (pintype "bidirectional"))
    )
    (net (code "85") (name "IN-A13") (class "Default")
      (node (ref "U7") (pin "2") (pinfunction "A1_2") (pintype "input"))
      (node (ref "XC1") (pin "P$36") (pinfunction "X36_P$36") (pintype "bidirectional"))
    )
    (net (code "86") (name "IN-A14") (class "Default")
      (node (ref "U8") (pin "11") (pinfunction "A1_11") (pintype "input"))
      (node (ref "XC1") (pin "P$10") (pinfunction "X10_P$10") (pintype "bidirectional"))
    )
    (net (code "87") (name "IN-A15") (class "Default")
      (node (ref "U7") (pin "11") (pinfunction "A1_11") (pintype "input"))
      (node (ref "XC1") (pin "P$9") (pinfunction "X9_P$9") (pintype "bidirectional"))
    )
    (net (code "88") (name "Net-(Q1-PadB)") (class "Default")
      (node (ref "Q1") (pin "B") (pinfunction "B_B") (pintype "passive"))
      (node (ref "R1") (pin "1") (pinfunction "1_1") (pintype "passive"))
      (node (ref "R3") (pin "1") (pinfunction "1_1") (pintype "passive"))
    )
    (net (code "89") (name "Net-(Q1-PadC)") (class "Default")
      (node (ref "Q1") (pin "C") (pinfunction "C_C") (pintype "passive"))
      (node (ref "SJ4") (pin "2") (pinfunction "2_2") (pintype "passive"))
    )
    (net (code "90") (name "Net-(U2-CLK)") (class "Default")
      (node (ref "U2") (pin "22") (pinfunction "CLK_22") (pintype "input"))
      (node (ref "U5") (pin "5") (pinfunction "Q_5") (pintype "output"))
    )
    (net (code "91") (name "Net-(U3-A14)") (class "Default")
      (node (ref "J8") (pin "2") (pinfunction "2_2") (pintype "passive"))
      (node (ref "U3") (pin "27") (pinfunction "A14_27") (pintype "input"))
    )
    (net (code "92") (name "Net-(U3-A15)") (class "Default")
      (node (ref "J9") (pin "2") (pinfunction "2_2") (pintype "passive"))
      (node (ref "U3") (pin "1") (pinfunction "A15_1") (pintype "input"))
    )
    (net (code "93") (name "Net-(U5A-D)") (class "Default")
      (node (ref "U5") (pin "2") (pinfunction "D_2") (pintype "input"))
      (node (ref "U5") (pin "6") (pinfunction "~{Q}_6") (pintype "output"))
    )
    (net (code "94") (name "R-SP01") (class "Default")
      (node (ref "J6") (pin "9") (pinfunction "9_9") (pintype "passive"))
      (node (ref "U6") (pin "18") (pinfunction "O2_18") (pintype "output"))
    )
    (net (code "95") (name "RAM-A14") (class "Default")
      (node (ref "U1") (pin "10") (pinfunction "A14_10") (pintype "input"))
      (node (ref "U6") (pin "19") (pinfunction "O1_19") (pintype "output"))
    )
    (net (code "96") (name "SND") (class "Default")
      (node (ref "J6") (pin "21") (pinfunction "21_21") (pintype "passive"))
      (node (ref "SJ4") (pin "1") (pinfunction "1_1") (pintype "passive"))
      (node (ref "XC1") (pin "P$2") (pinfunction "X2_P$2") (pintype "bidirectional"))
    )
    (net (code "97") (name "VCC") (class "Default")
      (node (ref "C1") (pin "2") (pinfunction "2_2") (pintype "passive"))
      (node (ref "C2") (pin "1") (pinfunction "1_1") (pintype "passive"))
      (node (ref "C3") (pin "2") (pinfunction "2_2") (pintype "passive"))
      (node (ref "C4") (pin "2") (pinfunction "2_2") (pintype "passive"))
      (node (ref "C5") (pin "2") (pinfunction "2_2") (pintype "passive"))
      (node (ref "C6") (pin "2") (pinfunction "2_2") (pintype "passive"))
      (node (ref "C7") (pin "2") (pinfunction "2_2") (pintype "passive"))
      (node (ref "C8") (pin "2") (pinfunction "2_2") (pintype "passive"))
      (node (ref "C9") (pin "+") (pinfunction "+_+") (pintype "passive"))
      (node (ref "J3") (pin "5") (pinfunction "5_5") (pintype "passive"))
      (node (ref "J4") (pin "10") (pinfunction "10_10") (pintype "passive"))
      (node (ref "J4") (pin "11") (pinfunction "11_11") (pintype "passive"))
      (node (ref "J5") (pin "5") (pinfunction "5_5") (pintype "passive"))
      (node (ref "J6") (pin "22") (pinfunction "22_22") (pintype "passive"))
      (node (ref "J8") (pin "3") (pinfunction "3_3") (pintype "passive"))
      (node (ref "J9") (pin "3") (pinfunction "3_3") (pintype "passive"))
      (node (ref "R3") (pin "2") (pinfunction "2_2") (pintype "passive"))
      (node (ref "U2") (pin "25") (pinfunction "A8_25") (pintype "bidirectional"))
      (node (ref "U2") (pin "28") (pinfunction "BC2_28") (pintype "bidirectional"))
      (node (ref "U2") (pin "40") (pinfunction "VCC_40") (pintype "power_in"))
      (node (ref "U3") (pin "28") (pinfunction "VCC_28") (pintype "power_in"))
      (node (ref "U4") (pin "20") (pinfunction "VCC_20") (pintype "power_in"))
      (node (ref "U5") (pin "1") (pinfunction "CLR_1") (pintype "input"))
      (node (ref "U5") (pin "4") (pinfunction "PRE_4") (pintype "input"))
      (node (ref "U6") (pin "20") (pinfunction "VCC_20") (pintype "power_in"))
      (node (ref "U9") (pin "3") (pinfunction "VCC_3") (pintype "power_in"))
      (node (ref "XC1") (pin "P$25") (pinfunction "X25_P$25") (pintype "bidirectional"))
    )
    (net (code "98") (name "unconnected-(U2-TST1-Pad39)") (class "Default")
      (node (ref "U2") (pin "39") (pinfunction "TST1_39") (pintype "bidirectional"))
    )
    (net (code "99") (name "unconnected-(U2-TST2-Pad26)") (class "Default")
      (node (ref "U2") (pin "26") (pinfunction "TST2_26") (pintype "bidirectional"))
    )
    (net (code "100") (name "unconnected-(U5B-CLK-Pad11)") (class "Default")
      (node (ref "U5") (pin "11") (pinfunction "CLK_11") (pintype "input"))
    )
    (net (code "101") (name "unconnected-(U5B-CLR-Pad13)") (class "Default")
      (node (ref "U5") (pin "13") (pinfunction "CLR_13") (pintype "input"))
    )
    (net (code "102") (name "unconnected-(U5B-D-Pad12)") (class "Default")
      (node (ref "U5") (pin "12") (pinfunction "D_12") (pintype "input"))
    )
    (net (code "103") (name "unconnected-(U5B-PRE-Pad10)") (class "Default")
      (node (ref "U5") (pin "10") (pinfunction "PRE_10") (pintype "input"))
    )
    (net (code "104") (name "unconnected-(U5B-Q-Pad9)") (class "Default")
      (node (ref "U5") (pin "9") (pinfunction "Q_9") (pintype "output"))
    )
    (net (code "105") (name "unconnected-(U5B-~{Q}-Pad8)") (class "Default")
      (node (ref "U5") (pin "8") (pinfunction "~{Q}_8") (pintype "output"))
    )
    (net (code "106") (name "Φ") (class "Default")
      (node (ref "J6") (pin "14") (pinfunction "14_14") (pintype "passive"))
      (node (ref "U5") (pin "3") (pinfunction "CLK_3") (pintype "input"))
      (node (ref "XC1") (pin "P$8") (pinfunction "X8_P$8") (pintype "bidirectional"))
    )
  )
)
